# mainboard.net
KiCad netlist of a schematic drawn in EAGLE
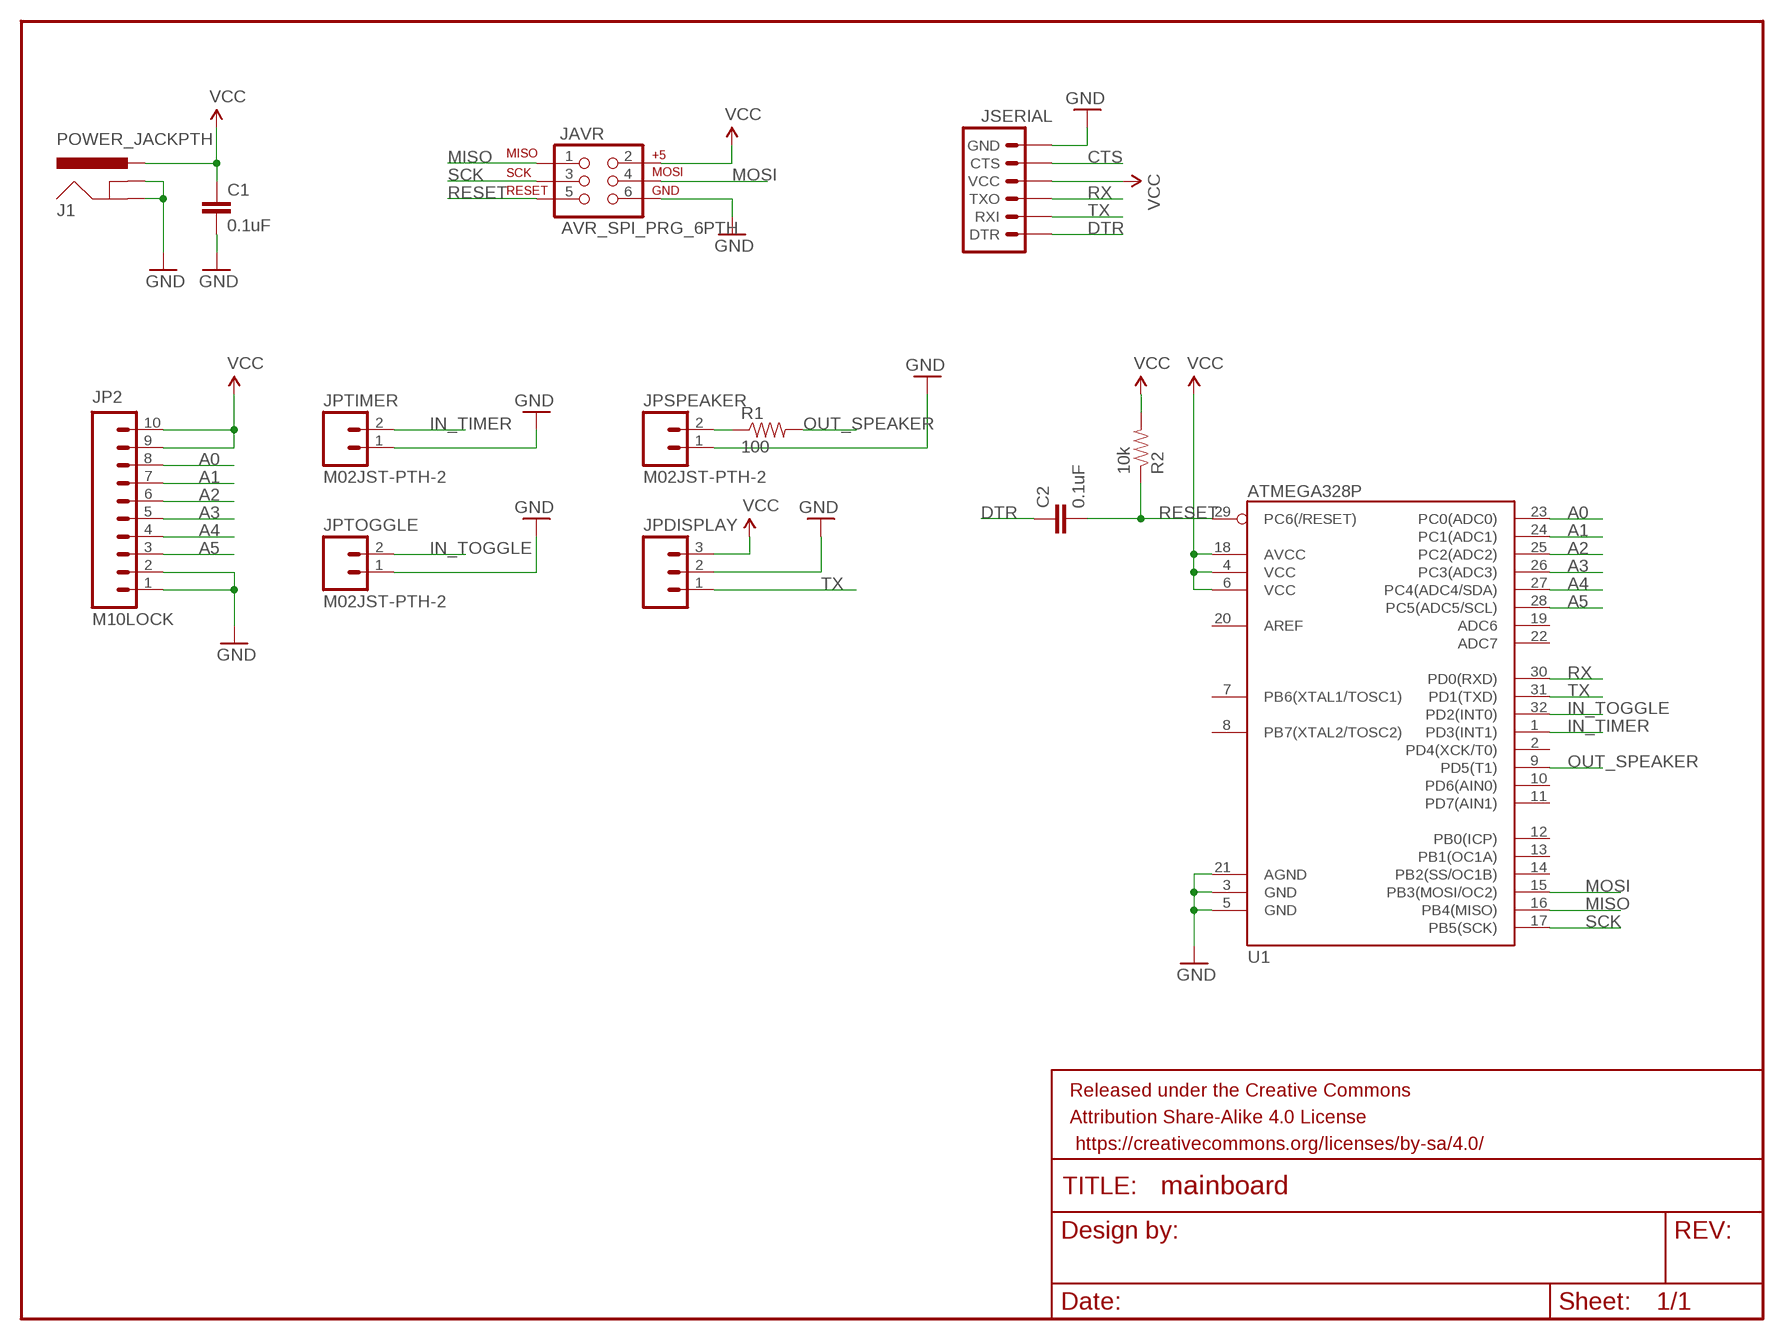
[diagram p0: schematic, sheet 1]

(export (version "E")
  (design (tool "Eeschema 10.0.6"))
  (components
    (comp (ref "C1")
      (value "0.1uF")
      (footprint "eagle-import:0603-CAP")
      (libsource (lib "eagle-import") (part "0.1UF-25V(+80/-20%)(0603)"))
    )
    (comp (ref "C2")
      (value "0.1uF")
      (footprint "eagle-import:0603-CAP")
      (libsource (lib "eagle-import") (part "0.1UF-25V(+80/-20%)(0603)"))
    )
    (comp (ref "FRAME1")
      (value "FRAME-LETTER")
      (footprint "eagle-import:CREATIVE_COMMONS")
      (libsource (lib "eagle-import") (part "FRAME-LETTER"))
    )
    (comp (ref "J1")
      (value "POWER_JACKPTH")
      (footprint "eagle-import:POWER_JACK_PTH")
      (libsource (lib "eagle-import") (part "POWER_JACKPTH"))
    )
    (comp (ref "JAVR")
      (value "AVR_SPI_PRG_6PTH")
      (footprint "eagle-import:2X3")
      (libsource (lib "eagle-import") (part "AVR_SPI_PRG_6PTH"))
    )
    (comp (ref "JP2")
      (value "M10LOCK")
      (footprint "eagle-import:1X10_LOCK")
      (libsource (lib "eagle-import") (part "M10LOCK"))
    )
    (comp (ref "JPDISPLAY")
      (value "M03JST-PTH")
      (footprint "eagle-import:JST-3-PTH")
      (libsource (lib "eagle-import") (part "M03JST-PTH"))
    )
    (comp (ref "JPSPEAKER")
      (value "M02JST-PTH-2")
      (footprint "eagle-import:JST-2-PTH")
      (libsource (lib "eagle-import") (part "M02JST-PTH-2"))
    )
    (comp (ref "JPTIMER")
      (value "M02JST-PTH-2")
      (footprint "eagle-import:JST-2-PTH")
      (libsource (lib "eagle-import") (part "M02JST-PTH-2"))
    )
    (comp (ref "JPTOGGLE")
      (value "M02JST-PTH-2")
      (footprint "eagle-import:JST-2-PTH")
      (libsource (lib "eagle-import") (part "M02JST-PTH-2"))
    )
    (comp (ref "JSERIAL")
      (value "ARDUINO_SERIAL_PROGRAMPTH")
      (footprint "eagle-import:1X06")
      (libsource (lib "eagle-import") (part "ARDUINO_SERIAL_PROGRAMPTH"))
    )
    (comp (ref "R1")
      (value "100")
      (footprint "eagle-import:0603-RES")
      (libsource (lib "eagle-import") (part "RESISTOR0603-RES"))
    )
    (comp (ref "R2")
      (value "10k")
      (footprint "eagle-import:0603-RES")
      (libsource (lib "eagle-import") (part "RESISTOR0603-RES"))
    )
    (comp (ref "U1")
      (value "ATMEGA328P")
      (footprint "eagle-import:TQFP32-08")
      (libsource (lib "eagle-import") (part "ATMEGA328_SMT"))
    )
  )
  (nets
    (net (code "1") (name "/A0") (class "Default")
      (node (ref "JP2") (pin "8") (pinfunction "8_8") (pintype "passive"))
      (node (ref "U1") (pin "23") (pinfunction "PC0(ADC0)_23") (pintype "bidirectional"))
    )
    (net (code "2") (name "/A1") (class "Default")
      (node (ref "JP2") (pin "7") (pinfunction "7_7") (pintype "passive"))
      (node (ref "U1") (pin "24") (pinfunction "PC1(ADC1)_24") (pintype "bidirectional"))
    )
    (net (code "3") (name "/A2") (class "Default")
      (node (ref "JP2") (pin "6") (pinfunction "6_6") (pintype "passive"))
      (node (ref "U1") (pin "25") (pinfunction "PC2(ADC2)_25") (pintype "bidirectional"))
    )
    (net (code "4") (name "/A3") (class "Default")
      (node (ref "JP2") (pin "5") (pinfunction "5_5") (pintype "passive"))
      (node (ref "U1") (pin "26") (pinfunction "PC3(ADC3)_26") (pintype "bidirectional"))
    )
    (net (code "5") (name "/A4") (class "Default")
      (node (ref "JP2") (pin "4") (pinfunction "4_4") (pintype "passive"))
      (node (ref "U1") (pin "27") (pinfunction "PC4(ADC4/SDA)_27") (pintype "bidirectional"))
    )
    (net (code "6") (name "/A5") (class "Default")
      (node (ref "JP2") (pin "3") (pinfunction "3_3") (pintype "passive"))
      (node (ref "U1") (pin "28") (pinfunction "PC5(ADC5/SCL)_28") (pintype "bidirectional"))
    )
    (net (code "7") (name "/CTS") (class "Default")
      (node (ref "JSERIAL") (pin "5") (pinfunction "CTS_5") (pintype "passive"))
    )
    (net (code "8") (name "/DTR") (class "Default")
      (node (ref "C2") (pin "1") (pinfunction "1_1") (pintype "passive"))
      (node (ref "JSERIAL") (pin "1") (pinfunction "DTR_1") (pintype "passive"))
    )
    (net (code "9") (name "/IN_TIMER") (class "Default")
      (node (ref "JPTIMER") (pin "2") (pinfunction "2_2") (pintype "passive"))
      (node (ref "U1") (pin "1") (pinfunction "PD3(INT1)_1") (pintype "bidirectional"))
    )
    (net (code "10") (name "/IN_TOGGLE") (class "Default")
      (node (ref "JPTOGGLE") (pin "2") (pinfunction "2_2") (pintype "passive"))
      (node (ref "U1") (pin "32") (pinfunction "PD2(INT0)_32") (pintype "bidirectional"))
    )
    (net (code "11") (name "/MISO") (class "Default")
      (node (ref "JAVR") (pin "1") (pinfunction "1_1") (pintype "passive"))
      (node (ref "U1") (pin "16") (pinfunction "PB4(MISO)_16") (pintype "bidirectional"))
    )
    (net (code "12") (name "/MOSI") (class "Default")
      (node (ref "JAVR") (pin "4") (pinfunction "4_4") (pintype "passive"))
      (node (ref "U1") (pin "15") (pinfunction "PB3(MOSI/OC2)_15") (pintype "bidirectional"))
    )
    (net (code "13") (name "/OUT_SPEAKER") (class "Default")
      (node (ref "R1") (pin "2") (pinfunction "2_2") (pintype "passive"))
      (node (ref "U1") (pin "9") (pinfunction "PD5(T1)_9") (pintype "bidirectional"))
    )
    (net (code "14") (name "/RESET") (class "Default")
      (node (ref "C2") (pin "2") (pinfunction "2_2") (pintype "passive"))
      (node (ref "JAVR") (pin "5") (pinfunction "5_5") (pintype "passive"))
      (node (ref "R2") (pin "1") (pinfunction "1_1") (pintype "passive"))
      (node (ref "U1") (pin "29") (pinfunction "PC6(/RESET)_29") (pintype "bidirectional"))
    )
    (net (code "15") (name "/RX") (class "Default")
      (node (ref "JSERIAL") (pin "3") (pinfunction "TXO_3") (pintype "passive"))
      (node (ref "U1") (pin "30") (pinfunction "PD0(RXD)_30") (pintype "bidirectional"))
    )
    (net (code "16") (name "/SCK") (class "Default")
      (node (ref "JAVR") (pin "3") (pinfunction "3_3") (pintype "passive"))
      (node (ref "U1") (pin "17") (pinfunction "PB5(SCK)_17") (pintype "bidirectional"))
    )
    (net (code "17") (name "/TX") (class "Default")
      (node (ref "JPDISPLAY") (pin "1") (pinfunction "1_1") (pintype "passive"))
      (node (ref "JSERIAL") (pin "2") (pinfunction "RXI_2") (pintype "passive"))
      (node (ref "U1") (pin "31") (pinfunction "PD1(TXD)_31") (pintype "bidirectional"))
    )
    (net (code "18") (name "GND") (class "Default")
      (node (ref "C1") (pin "2") (pinfunction "2_2") (pintype "passive"))
      (node (ref "J1") (pin "GND") (pinfunction "GND_GND") (pintype "bidirectional"))
      (node (ref "J1") (pin "GNDBREAK") (pinfunction "GNDBREAK_GNDBREAK") (pintype "bidirectional"))
      (node (ref "JAVR") (pin "6") (pinfunction "6_6") (pintype "passive"))
      (node (ref "JP2") (pin "1") (pinfunction "1_1") (pintype "passive"))
      (node (ref "JP2") (pin "2") (pinfunction "2_2") (pintype "passive"))
      (node (ref "JPDISPLAY") (pin "2") (pinfunction "2_2") (pintype "passive"))
      (node (ref "JPSPEAKER") (pin "1") (pinfunction "1_1") (pintype "passive"))
      (node (ref "JPTIMER") (pin "1") (pinfunction "1_1") (pintype "passive"))
      (node (ref "JPTOGGLE") (pin "1") (pinfunction "1_1") (pintype "passive"))
      (node (ref "JSERIAL") (pin "6") (pinfunction "GND_6") (pintype "passive"))
      (node (ref "U1") (pin "21") (pinfunction "AGND_21") (pintype "bidirectional"))
      (node (ref "U1") (pin "3") (pinfunction "GND_3") (pintype "bidirectional"))
      (node (ref "U1") (pin "5") (pinfunction "GND_5") (pintype "bidirectional"))
    )
    (net (code "19") (name "Net-(JPSPEAKER-Pad2)") (class "Default")
      (node (ref "JPSPEAKER") (pin "2") (pinfunction "2_2") (pintype "passive"))
      (node (ref "R1") (pin "1") (pinfunction "1_1") (pintype "passive"))
    )
    (net (code "20") (name "VCC") (class "Default")
      (node (ref "C1") (pin "1") (pinfunction "1_1") (pintype "passive"))
      (node (ref "J1") (pin "PWR") (pinfunction "PWR_PWR") (pintype "bidirectional"))
      (node (ref "JAVR") (pin "2") (pinfunction "2_2") (pintype "passive"))
      (node (ref "JP2") (pin "10") (pinfunction "10_10") (pintype "passive"))
      (node (ref "JP2") (pin "9") (pinfunction "9_9") (pintype "passive"))
      (node (ref "JPDISPLAY") (pin "3") (pinfunction "3_3") (pintype "passive"))
      (node (ref "JSERIAL") (pin "4") (pinfunction "VCC_4") (pintype "passive"))
      (node (ref "R2") (pin "2") (pinfunction "2_2") (pintype "passive"))
      (node (ref "U1") (pin "18") (pinfunction "AVCC_18") (pintype "bidirectional"))
      (node (ref "U1") (pin "4") (pinfunction "VCC_4") (pintype "bidirectional"))
      (node (ref "U1") (pin "6") (pinfunction "VCC_6") (pintype "bidirectional"))
    )
    (net (code "21") (name "unconnected-(U1-ADC6-Pad19)") (class "Default")
      (node (ref "U1") (pin "19") (pinfunction "ADC6_19") (pintype "bidirectional"))
    )
    (net (code "22") (name "unconnected-(U1-ADC7-Pad22)") (class "Default")
      (node (ref "U1") (pin "22") (pinfunction "ADC7_22") (pintype "bidirectional"))
    )
    (net (code "23") (name "unconnected-(U1-AREF-Pad20)") (class "Default")
      (node (ref "U1") (pin "20") (pinfunction "AREF_20") (pintype "bidirectional"))
    )
    (net (code "24") (name "unconnected-(U1-PB0(ICP)-Pad12)") (class "Default")
      (node (ref "U1") (pin "12") (pinfunction "PB0(ICP)_12") (pintype "bidirectional"))
    )
    (net (code "25") (name "unconnected-(U1-PB1(OC1A)-Pad13)") (class "Default")
      (node (ref "U1") (pin "13") (pinfunction "PB1(OC1A)_13") (pintype "bidirectional"))
    )
    (net (code "26") (name "unconnected-(U1-PB2(SS{slash}OC1B)-Pad14)") (class "Default")
      (node (ref "U1") (pin "14") (pinfunction "PB2(SS/OC1B)_14") (pintype "bidirectional"))
    )
    (net (code "27") (name "unconnected-(U1-PB6(XTAL1{slash}TOSC1)-Pad7)") (class "Default")
      (node (ref "U1") (pin "7") (pinfunction "PB6(XTAL1/TOSC1)_7") (pintype "bidirectional"))
    )
    (net (code "28") (name "unconnected-(U1-PB7(XTAL2{slash}TOSC2)-Pad8)") (class "Default")
      (node (ref "U1") (pin "8") (pinfunction "PB7(XTAL2/TOSC2)_8") (pintype "bidirectional"))
    )
    (net (code "29") (name "unconnected-(U1-PD4(XCK{slash}T0)-Pad2)") (class "Default")
      (node (ref "U1") (pin "2") (pinfunction "PD4(XCK/T0)_2") (pintype "bidirectional"))
    )
    (net (code "30") (name "unconnected-(U1-PD6(AIN0)-Pad10)") (class "Default")
      (node (ref "U1") (pin "10") (pinfunction "PD6(AIN0)_10") (pintype "bidirectional"))
    )
    (net (code "31") (name "unconnected-(U1-PD7(AIN1)-Pad11)") (class "Default")
      (node (ref "U1") (pin "11") (pinfunction "PD7(AIN1)_11") (pintype "bidirectional"))
    )
  )
)
